# ATMega1284p.net
KiCad netlist of a schematic drawn in Altium Designer
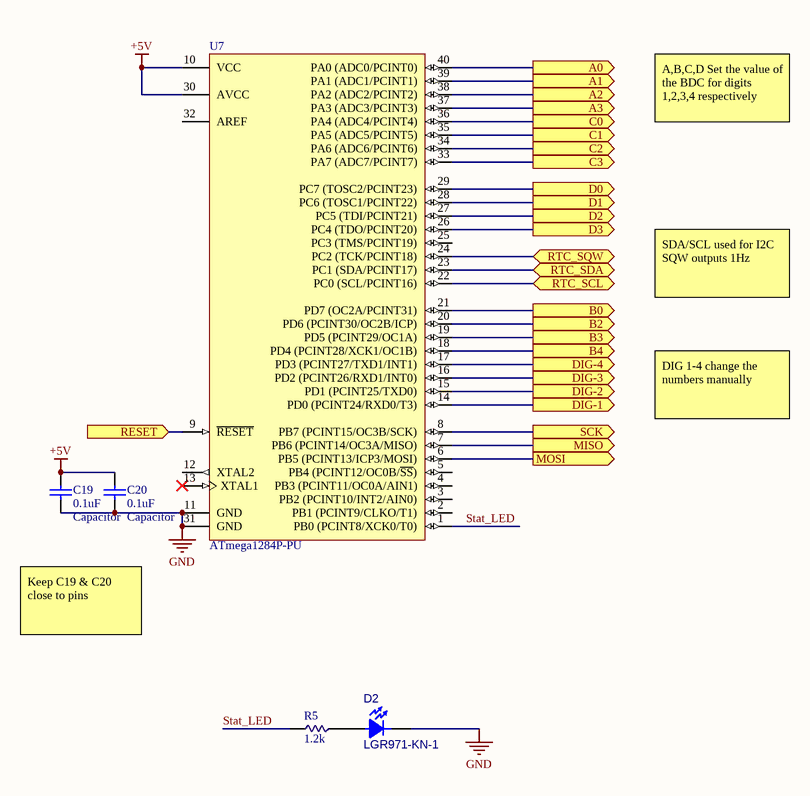
[diagram p0: ATMega1284p.SchDoc]

(export (version "E")
  (design (tool "Eeschema 10.0.6"))
  (components
    (comp (ref "C19")
      (value "0.1uF")
      (footprint "FOOTPRINT-1206-GEN")
      (description "CAP CER 0.1UF 50V X7R 1206")
      (fields
        (field (name "PART NUMBER") "1276-7034-1-ND")
        (field (name "TYPE") "Capacitor")
        (field (name "Comment") "Capacitor - 0.1uF - 1206")
        (field (name "PUBLISHER") "Altium Limited")
      )
      (libsource (lib "") (part "Symbol_1"))
    )
    (comp (ref "C20")
      (value "0.1uF")
      (footprint "FOOTPRINT-1206-GEN")
      (description "CAP CER 0.1UF 50V X7R 1206")
      (fields
        (field (name "PART NUMBER") "1276-7034-1-ND")
        (field (name "TYPE") "Capacitor")
        (field (name "Comment") "Capacitor - 0.1uF - 1206")
        (field (name "PUBLISHER") "Altium Limited")
      )
      (libsource (lib "") (part "Symbol_1"))
    )
    (comp (ref "D2")
      (value "LGR971-KN-1")
      (footprint "FOOTPRINT-OSRAM-CHIPLED-0805-1A2K")
      (description "LED Uni-Color Green 572nm 2-Pin Chip 0805(2012Metric) T/R")
      (fields (field (name "PART NUMBER") "475-1410-1-ND"))
      (libsource (lib "") (part "Symbol_2"))
    )
    (comp (ref "R5")
      (value "1.2k")
      (footprint "FOOTPRINT-0805-GEN")
      (description "Res Thick Film 0805 1.2K Ohm 1% 0.125W ±100ppm/°C Molded SMD Paper T/R")
      (fields (field (name "Comment") "RMCF0805FT1K20"))
      (libsource (lib "University of California Riverside - FSAE") (part "Symbol"))
    )
    (comp (ref "U7")
      (value "ATmega1284P-PU")
      (footprint "40P6")
      (libsource (lib "Altium Content Vault") (part "MC-8B-ATM128-IL40"))
    )
  )
  (nets
    (net (code "1") (name "+5V") (class "Default")
      (node (ref "C19") (pin "2") (pinfunction "2_2") (pintype "passive"))
      (node (ref "C20") (pin "2") (pinfunction "2_2") (pintype "passive"))
      (node (ref "U7") (pin "10") (pinfunction "VCC_10") (pintype "power_in"))
      (node (ref "U7") (pin "30") (pinfunction "AVCC_30") (pintype "power_in"))
    )
    (net (code "2") (name "/A0") (class "Default")
      (node (ref "U7") (pin "40") (pinfunction "PA0_(ADC0/PCINT0)_40") (pintype "bidirectional"))
    )
    (net (code "3") (name "/A1") (class "Default")
      (node (ref "U7") (pin "39") (pinfunction "PA1_(ADC1/PCINT1)_39") (pintype "bidirectional"))
    )
    (net (code "4") (name "/A2") (class "Default")
      (node (ref "U7") (pin "38") (pinfunction "PA2_(ADC2/PCINT2)_38") (pintype "bidirectional"))
    )
    (net (code "5") (name "/A3") (class "Default")
      (node (ref "U7") (pin "37") (pinfunction "PA3_(ADC3/PCINT3)_37") (pintype "bidirectional"))
    )
    (net (code "6") (name "/B0") (class "Default")
      (node (ref "U7") (pin "21") (pinfunction "PD7_(OC2A/PCINT31)_21") (pintype "bidirectional"))
    )
    (net (code "7") (name "/B2") (class "Default")
      (node (ref "U7") (pin "20") (pinfunction "PD6_(PCINT30/OC2B/ICP)_20") (pintype "bidirectional"))
    )
    (net (code "8") (name "/B3") (class "Default")
      (node (ref "U7") (pin "19") (pinfunction "PD5_(PCINT29/OC1A)_19") (pintype "bidirectional"))
    )
    (net (code "9") (name "/B4") (class "Default")
      (node (ref "U7") (pin "18") (pinfunction "PD4_(PCINT28/XCK1/OC1B)_18") (pintype "bidirectional"))
    )
    (net (code "10") (name "/C0") (class "Default")
      (node (ref "U7") (pin "36") (pinfunction "PA4_(ADC4/PCINT4)_36") (pintype "bidirectional"))
    )
    (net (code "11") (name "/C1") (class "Default")
      (node (ref "U7") (pin "35") (pinfunction "PA5_(ADC5/PCINT5)_35") (pintype "bidirectional"))
    )
    (net (code "12") (name "/C2") (class "Default")
      (node (ref "U7") (pin "34") (pinfunction "PA6_(ADC6/PCINT6)_34") (pintype "bidirectional"))
    )
    (net (code "13") (name "/C3") (class "Default")
      (node (ref "U7") (pin "33") (pinfunction "PA7_(ADC7/PCINT7)_33") (pintype "bidirectional"))
    )
    (net (code "14") (name "/D0") (class "Default")
      (node (ref "U7") (pin "29") (pinfunction "PC7_(TOSC2/PCINT23)_29") (pintype "bidirectional"))
    )
    (net (code "15") (name "/D1") (class "Default")
      (node (ref "U7") (pin "28") (pinfunction "PC6_(TOSC1/PCINT22)_28") (pintype "bidirectional"))
    )
    (net (code "16") (name "/D2") (class "Default")
      (node (ref "U7") (pin "27") (pinfunction "PC5_(TDI/PCINT21)_27") (pintype "bidirectional"))
    )
    (net (code "17") (name "/D3") (class "Default")
      (node (ref "U7") (pin "26") (pinfunction "PC4_(TDO/PCINT20)_26") (pintype "bidirectional"))
    )
    (net (code "18") (name "/DIG-1") (class "Default")
      (node (ref "U7") (pin "14") (pinfunction "PD0_(PCINT24/RXD0/T3)_14") (pintype "bidirectional"))
    )
    (net (code "19") (name "/DIG-2") (class "Default")
      (node (ref "U7") (pin "15") (pinfunction "PD1_(PCINT25/TXD0)_15") (pintype "bidirectional"))
    )
    (net (code "20") (name "/DIG-3") (class "Default")
      (node (ref "U7") (pin "16") (pinfunction "PD2_(PCINT26/RXD1/INT0)_16") (pintype "bidirectional"))
    )
    (net (code "21") (name "/DIG-4") (class "Default")
      (node (ref "U7") (pin "17") (pinfunction "PD3_(PCINT27/TXD1/INT1)_17") (pintype "bidirectional"))
    )
    (net (code "22") (name "/MISO") (class "Default")
      (node (ref "U7") (pin "7") (pinfunction "PB6_(PCINT14/OC3A/MISO)_7") (pintype "bidirectional"))
    )
    (net (code "23") (name "/MOSI") (class "Default")
      (node (ref "U7") (pin "6") (pinfunction "PB5_(PCINT13/ICP3/MOSI)_6") (pintype "bidirectional"))
    )
    (net (code "24") (name "/RESET") (class "Default")
      (node (ref "U7") (pin "9") (pinfunction "~{RESET}_9") (pintype "input"))
    )
    (net (code "25") (name "/RTC_SCL") (class "Default")
      (node (ref "U7") (pin "22") (pinfunction "PC0_(SCL/PCINT16)_22") (pintype "bidirectional"))
    )
    (net (code "26") (name "/RTC_SDA") (class "Default")
      (node (ref "U7") (pin "23") (pinfunction "PC1_(SDA/PCINT17)_23") (pintype "bidirectional"))
    )
    (net (code "27") (name "/RTC_SQW") (class "Default")
      (node (ref "U7") (pin "24") (pinfunction "PC2_(TCK/PCINT18)_24") (pintype "bidirectional"))
    )
    (net (code "28") (name "/SCK") (class "Default")
      (node (ref "U7") (pin "8") (pinfunction "PB7_(PCINT15/OC3B/SCK)_8") (pintype "bidirectional"))
    )
    (net (code "29") (name "/Stat_LED") (class "Default")
      (node (ref "R5") (pin "2") (pinfunction "2_2") (pintype "passive"))
      (node (ref "U7") (pin "1") (pinfunction "PB0_(PCINT8/XCK0/T0)_1") (pintype "bidirectional"))
    )
    (net (code "30") (name "GND") (class "Default")
      (node (ref "C19") (pin "1") (pinfunction "1_1") (pintype "passive"))
      (node (ref "C20") (pin "1") (pinfunction "1_1") (pintype "passive"))
      (node (ref "D2") (pin "2") (pinfunction "K_2") (pintype "passive"))
      (node (ref "U7") (pin "11") (pinfunction "GND_11") (pintype "power_in"))
      (node (ref "U7") (pin "31") (pinfunction "GND_31") (pintype "power_in"))
    )
    (net (code "31") (name "Net-(D2-A)") (class "Default")
      (node (ref "D2") (pin "1") (pinfunction "A_1") (pintype "passive"))
      (node (ref "R5") (pin "1") (pinfunction "1_1") (pintype "passive"))
    )
    (net (code "32") (name "unconnected-(U7-AREF-Pad32)") (class "Default")
      (node (ref "U7") (pin "32") (pinfunction "AREF_32") (pintype "power_in"))
    )
    (net (code "33") (name "unconnected-(U7-PB1_(PCINT9{slash}CLKO{slash}T1)-Pad2)") (class "Default")
      (node (ref "U7") (pin "2") (pinfunction "PB1_(PCINT9/CLKO/T1)_2") (pintype "bidirectional"))
    )
    (net (code "34") (name "unconnected-(U7-PB2_(PCINT10{slash}INT2{slash}AIN0)-Pad3)") (class "Default")
      (node (ref "U7") (pin "3") (pinfunction "PB2_(PCINT10/INT2/AIN0)_3") (pintype "bidirectional"))
    )
    (net (code "35") (name "unconnected-(U7-PB3_(PCINT11{slash}OC0A{slash}AIN1)-Pad4)") (class "Default")
      (node (ref "U7") (pin "4") (pinfunction "PB3_(PCINT11/OC0A/AIN1)_4") (pintype "bidirectional"))
    )
    (net (code "36") (name "unconnected-(U7-PB4_(PCINT12{slash}OC0B{slash}~{SS})-Pad5)") (class "Default")
      (node (ref "U7") (pin "5") (pinfunction "PB4_(PCINT12/OC0B/~{SS})_5") (pintype "bidirectional"))
    )
    (net (code "37") (name "unconnected-(U7-PC3_(TMS{slash}PCINT19)-Pad25)") (class "Default")
      (node (ref "U7") (pin "25") (pinfunction "PC3_(TMS/PCINT19)_25") (pintype "bidirectional"))
    )
    (net (code "38") (name "unconnected-(U7-XTAL1-Pad13)") (class "Default")
      (node (ref "U7") (pin "13") (pinfunction "XTAL1_13") (pintype "input+no_connect"))
    )
    (net (code "39") (name "unconnected-(U7-XTAL2-Pad12)") (class "Default")
      (node (ref "U7") (pin "12") (pinfunction "XTAL2_12") (pintype "output"))
    )
  )
)
